# USB_SPI_Flash.net
KiCad netlist of a schematic drawn in Altium Designer
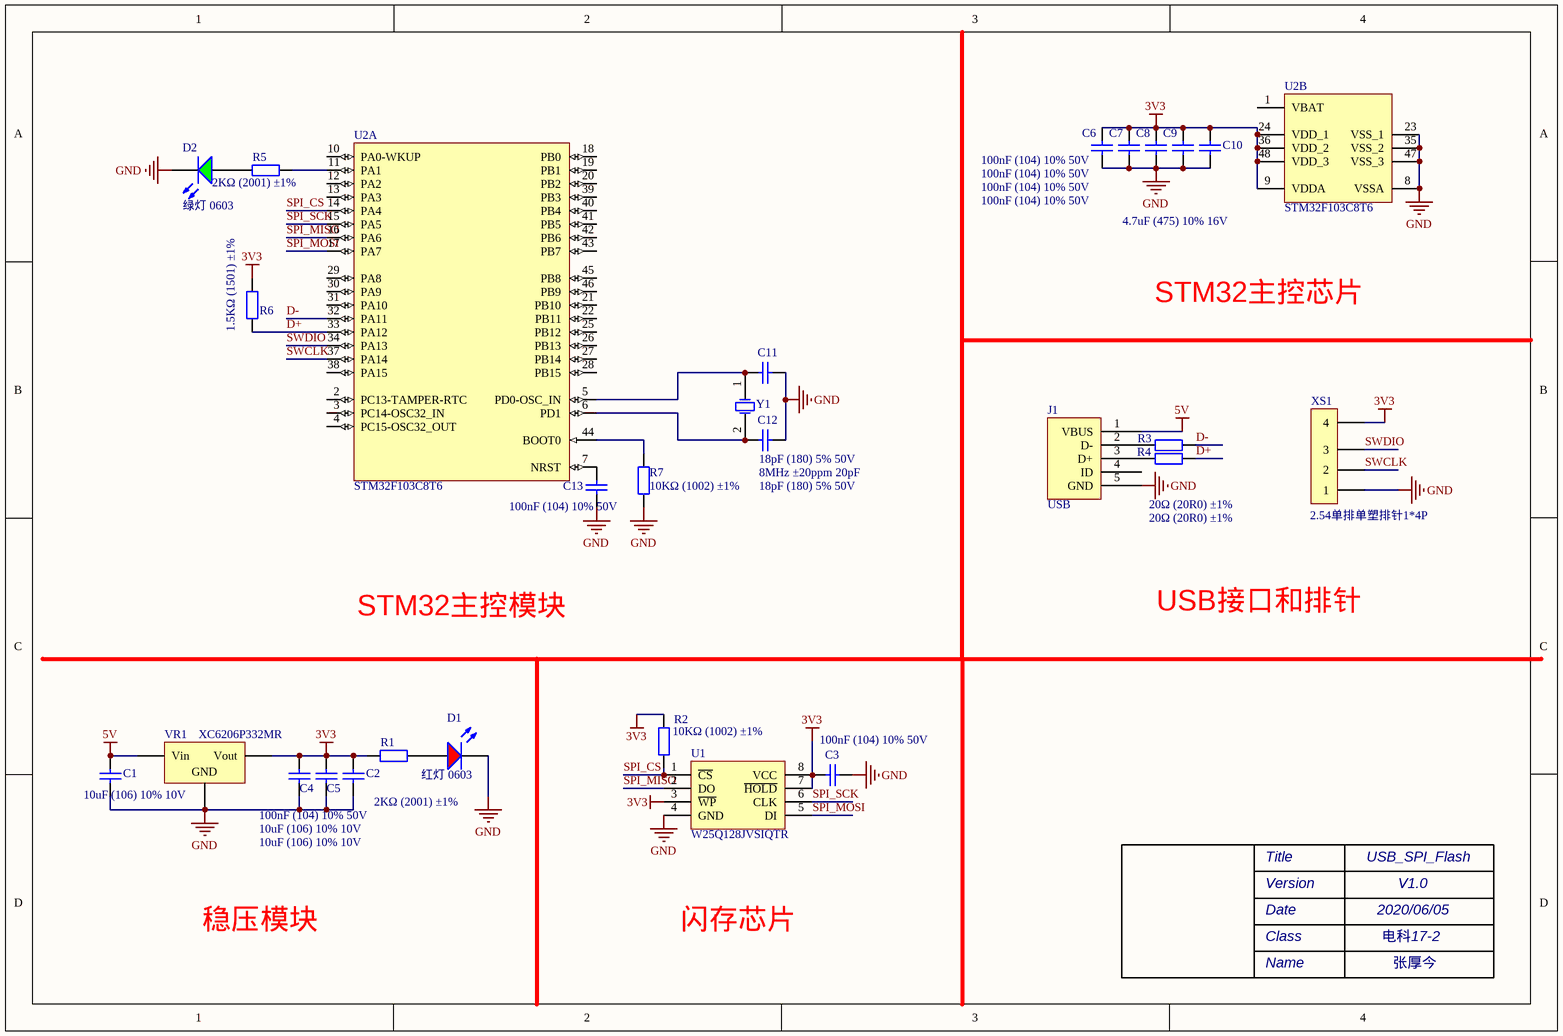
[diagram p0: USB_SPI_Flash.SchDoc]

(export (version "E")
  (design (tool "Eeschema 10.0.6"))
  (components
    (comp (ref "C1")
      (value "10uF (106) 10% 10V")
      (footprint "0603_C")
      (description "贴片电容")
      (libsource (lib "Cap") (part "0603 10uF (106) 10% 10V"))
    )
    (comp (ref "C2")
      (value "100nF (104) 10% 50V")
      (footprint "0603_C")
      (description "贴片电容")
      (libsource (lib "Cap") (part "0603 100nF (104) 10% 50V"))
    )
    (comp (ref "C3")
      (value "100nF (104) 10% 50V")
      (footprint "0603_C")
      (description "贴片电容")
      (libsource (lib "Cap") (part "0603 100nF (104) 10% 50V"))
    )
    (comp (ref "C4")
      (value "10uF (106) 10% 10V")
      (footprint "0603_C")
      (description "贴片电容")
      (libsource (lib "Cap") (part "0603 10uF (106) 10% 10V"))
    )
    (comp (ref "C5")
      (value "10uF (106) 10% 10V")
      (footprint "0603_C")
      (description "贴片电容")
      (libsource (lib "Cap") (part "0603 10uF (106) 10% 10V"))
    )
    (comp (ref "C6")
      (value "100nF (104) 10% 50V")
      (footprint "0603_C")
      (description "贴片电容")
      (libsource (lib "Cap") (part "0603 100nF (104) 10% 50V"))
    )
    (comp (ref "C7")
      (value "100nF (104) 10% 50V")
      (footprint "0603_C")
      (description "贴片电容")
      (libsource (lib "Cap") (part "0603 100nF (104) 10% 50V"))
    )
    (comp (ref "C8")
      (value "100nF (104) 10% 50V")
      (footprint "0603_C")
      (description "贴片电容")
      (libsource (lib "Cap") (part "0603 100nF (104) 10% 50V"))
    )
    (comp (ref "C9")
      (value "100nF (104) 10% 50V")
      (footprint "0603_C")
      (description "贴片电容")
      (libsource (lib "Cap") (part "0603 100nF (104) 10% 50V"))
    )
    (comp (ref "C10")
      (value "4.7uF (475) 10% 16V")
      (footprint "0603_C")
      (description "贴片电容")
      (libsource (lib "Cap") (part "0603 4.7uF (475) 10% 16V"))
    )
    (comp (ref "C11")
      (value "18pF (180) 5% 50V")
      (footprint "0603_C")
      (description "贴片电容")
      (libsource (lib "Cap") (part "0603 18pF (180) 5% 50V"))
    )
    (comp (ref "C12")
      (value "18pF (180) 5% 50V")
      (footprint "0603_C")
      (description "贴片电容")
      (libsource (lib "Cap") (part "0603 18pF (180) 5% 50V"))
    )
    (comp (ref "C13")
      (value "100nF (104) 10% 50V")
      (footprint "0603_C")
      (description "贴片电容")
      (libsource (lib "Cap") (part "0603 100nF (104) 10% 50V"))
    )
    (comp (ref "D1")
      (value "红灯 0603")
      (footprint "0603_LED_S1")
      (description "发光二极管")
      (libsource (lib "LED") (part "0603 红灯"))
    )
    (comp (ref "D2")
      (value "绿灯 0603")
      (footprint "0603_LED_S1")
      (description "发光二极管")
      (libsource (lib "LED") (part "0603 绿灯"))
    )
    (comp (ref "J1")
      (value "USB")
      (footprint "GOLDFIGER_FPC_4")
      (libsource (lib "USB_SPI_Flash") (part "USB"))
    )
    (comp (ref "R1")
      (value "2KΩ (2001) ±1%")
      (footprint "0603_R")
      (description "贴片电阻")
      (libsource (lib "RES") (part "0603 2KΩ (2001) 1%"))
    )
    (comp (ref "R2")
      (value "10KΩ (1002) ±1%")
      (footprint "0603_R")
      (description "贴片电阻")
      (libsource (lib "RES") (part "0603 10KΩ (1002) 1%"))
    )
    (comp (ref "R3")
      (value "20Ω (20R0) ±1%")
      (footprint "0603_R")
      (description "贴片电阻")
      (libsource (lib "RES") (part "0603 20Ω (20R0) 1%"))
    )
    (comp (ref "R4")
      (value "20Ω (20R0) ±1%")
      (footprint "0603_R")
      (description "贴片电阻")
      (libsource (lib "RES") (part "0603 20Ω (20R0) 1%"))
    )
    (comp (ref "R5")
      (value "2KΩ (2001) ±1%")
      (footprint "0603_R")
      (description "贴片电阻")
      (libsource (lib "RES") (part "0603 2KΩ (2001) 1%"))
    )
    (comp (ref "R6")
      (value "1.5KΩ (1501) ±1%")
      (footprint "0603_R")
      (description "贴片电阻")
      (libsource (lib "RES") (part "0603 1.5KΩ (1501) 1%"))
    )
    (comp (ref "R7")
      (value "10KΩ (1002) ±1%")
      (footprint "0603_R")
      (description "贴片电阻")
      (libsource (lib "RES") (part "0603 10KΩ (1002) 1%"))
    )
    (comp (ref "U1")
      (value "W25Q128JVSIQTR")
      (footprint "SOIC-8_208mil")
      (description "Flash ROM")
      (libsource (lib "IC") (part "W25Q128JVSIQTR_[C97521]"))
    )
    (comp (ref "U2")
      (value "STM32F103C8T6")
      (footprint "LQFP-48_7x7x05P")
      (description "ARM")
      (libsource (lib "MCU") (part "STM32F103C8T6"))
    )
    (comp (ref "VR1")
      (value "XC6206P332MR")
      (footprint "SOT-23-3L")
      (description "低压差线性稳压(LDO)")
      (libsource (lib "LDO") (part "SOT-23 XC6206P332MR"))
    )
    (comp (ref "XS1")
      (value "2.54单排单塑排针1*4P")
      (footprint "PIN4")
      (libsource (lib "USB_SPI_Flash") (part "2.54单排单塑排针1*4P"))
    )
    (comp (ref "Y1")
      (value "8MHz ±20ppm 20pF")
      (footprint "SMD-5032_2P")
      (description "贴片晶振")
      (libsource (lib "CrystalOscillator") (part "SMD-5032_2P 8MHz 20ppm 20pF"))
    )
  )
  (nets
    (net (code "1") (name "/D+") (class "Default")
      (node (ref "R4") (pin "2") (pinfunction "2_2") (pintype "passive"))
      (node (ref "R6") (pin "1") (pinfunction "1_1") (pintype "passive"))
      (node (ref "U2") (pin "33") (pinfunction "PA12_33") (pintype "bidirectional"))
    )
    (net (code "2") (name "/D-") (class "Default")
      (node (ref "R3") (pin "2") (pinfunction "2_2") (pintype "passive"))
      (node (ref "U2") (pin "32") (pinfunction "PA11_32") (pintype "bidirectional"))
    )
    (net (code "3") (name "/SPI_CS") (class "Default")
      (node (ref "R2") (pin "1") (pinfunction "1_1") (pintype "passive"))
      (node (ref "U1") (pin "1") (pinfunction "~{CS}_1") (pintype "passive"))
      (node (ref "U2") (pin "14") (pinfunction "PA4_14") (pintype "bidirectional"))
    )
    (net (code "4") (name "/SPI_MISO") (class "Default")
      (node (ref "U1") (pin "2") (pinfunction "DO_2") (pintype "passive"))
      (node (ref "U2") (pin "16") (pinfunction "PA6_16") (pintype "bidirectional"))
    )
    (net (code "5") (name "/SPI_MOSI") (class "Default")
      (node (ref "U1") (pin "5") (pinfunction "DI_5") (pintype "passive"))
      (node (ref "U2") (pin "17") (pinfunction "PA7_17") (pintype "bidirectional"))
    )
    (net (code "6") (name "/SPI_SCK") (class "Default")
      (node (ref "U1") (pin "6") (pinfunction "CLK_6") (pintype "passive"))
      (node (ref "U2") (pin "15") (pinfunction "PA5_15") (pintype "bidirectional"))
    )
    (net (code "7") (name "/SWCLK") (class "Default")
      (node (ref "U2") (pin "37") (pinfunction "PA14_37") (pintype "bidirectional"))
      (node (ref "XS1") (pin "2") (pinfunction "2_2") (pintype "passive"))
    )
    (net (code "8") (name "/SWDIO") (class "Default")
      (node (ref "U2") (pin "34") (pinfunction "PA13_34") (pintype "bidirectional"))
      (node (ref "XS1") (pin "3") (pinfunction "3_3") (pintype "passive"))
    )
    (net (code "9") (name "3V3") (class "Default")
      (node (ref "C10") (pin "2") (pinfunction "2_2") (pintype "passive"))
      (node (ref "C2") (pin "2") (pinfunction "2_2") (pintype "passive"))
      (node (ref "C3") (pin "2") (pinfunction "2_2") (pintype "passive"))
      (node (ref "C4") (pin "2") (pinfunction "2_2") (pintype "passive"))
      (node (ref "C5") (pin "2") (pinfunction "2_2") (pintype "passive"))
      (node (ref "C6") (pin "2") (pinfunction "2_2") (pintype "passive"))
      (node (ref "C7") (pin "2") (pinfunction "2_2") (pintype "passive"))
      (node (ref "C8") (pin "2") (pinfunction "2_2") (pintype "passive"))
      (node (ref "C9") (pin "2") (pinfunction "2_2") (pintype "passive"))
      (node (ref "R1") (pin "2") (pinfunction "2_2") (pintype "passive"))
      (node (ref "R2") (pin "2") (pinfunction "2_2") (pintype "passive"))
      (node (ref "R6") (pin "2") (pinfunction "2_2") (pintype "passive"))
      (node (ref "U1") (pin "3") (pinfunction "~{WP}_3") (pintype "passive"))
      (node (ref "U1") (pin "7") (pinfunction "~{HOLD}_7") (pintype "passive"))
      (node (ref "U1") (pin "8") (pinfunction "VCC_8") (pintype "passive"))
      (node (ref "U2") (pin "24") (pinfunction "VDD_1_24") (pintype "power_in"))
      (node (ref "U2") (pin "36") (pinfunction "VDD_2_36") (pintype "power_in"))
      (node (ref "U2") (pin "48") (pinfunction "VDD_3_48") (pintype "power_in"))
      (node (ref "U2") (pin "9") (pinfunction "VDDA_9") (pintype "power_in"))
      (node (ref "VR1") (pin "2") (pinfunction "Vout_2") (pintype "passive"))
      (node (ref "XS1") (pin "4") (pinfunction "4_4") (pintype "passive"))
    )
    (net (code "10") (name "5V") (class "Default")
      (node (ref "C1") (pin "2") (pinfunction "2_2") (pintype "passive"))
      (node (ref "J1") (pin "1") (pinfunction "VBUS_1") (pintype "passive"))
      (node (ref "VR1") (pin "3") (pinfunction "Vin_3") (pintype "passive"))
    )
    (net (code "11") (name "GND") (class "Default")
      (node (ref "C1") (pin "1") (pinfunction "1_1") (pintype "passive"))
      (node (ref "C10") (pin "1") (pinfunction "1_1") (pintype "passive"))
      (node (ref "C11") (pin "1") (pinfunction "1_1") (pintype "passive"))
      (node (ref "C12") (pin "1") (pinfunction "1_1") (pintype "passive"))
      (node (ref "C13") (pin "1") (pinfunction "1_1") (pintype "passive"))
      (node (ref "C2") (pin "1") (pinfunction "1_1") (pintype "passive"))
      (node (ref "C3") (pin "1") (pinfunction "1_1") (pintype "passive"))
      (node (ref "C4") (pin "1") (pinfunction "1_1") (pintype "passive"))
      (node (ref "C5") (pin "1") (pinfunction "1_1") (pintype "passive"))
      (node (ref "C6") (pin "1") (pinfunction "1_1") (pintype "passive"))
      (node (ref "C7") (pin "1") (pinfunction "1_1") (pintype "passive"))
      (node (ref "C8") (pin "1") (pinfunction "1_1") (pintype "passive"))
      (node (ref "C9") (pin "1") (pinfunction "1_1") (pintype "passive"))
      (node (ref "D1") (pin "K") (pinfunction "K_K") (pintype "passive"))
      (node (ref "D2") (pin "K") (pinfunction "K_K") (pintype "passive"))
      (node (ref "J1") (pin "5") (pinfunction "GND_5") (pintype "passive"))
      (node (ref "R7") (pin "1") (pinfunction "1_1") (pintype "passive"))
      (node (ref "U1") (pin "4") (pinfunction "GND_4") (pintype "passive"))
      (node (ref "U2") (pin "23") (pinfunction "VSS_1_23") (pintype "power_in"))
      (node (ref "U2") (pin "35") (pinfunction "VSS_2_35") (pintype "power_in"))
      (node (ref "U2") (pin "47") (pinfunction "VSS_3_47") (pintype "power_in"))
      (node (ref "U2") (pin "8") (pinfunction "VSSA_8") (pintype "power_in"))
      (node (ref "VR1") (pin "1") (pinfunction "GND_1") (pintype "passive"))
      (node (ref "XS1") (pin "1") (pinfunction "1_1") (pintype "passive"))
    )
    (net (code "12") (name "Net-(D1-PadA)") (class "Default")
      (node (ref "D1") (pin "A") (pinfunction "A_A") (pintype "passive"))
      (node (ref "R1") (pin "1") (pinfunction "1_1") (pintype "passive"))
    )
    (net (code "13") (name "Net-(D2-PadA)") (class "Default")
      (node (ref "D2") (pin "A") (pinfunction "A_A") (pintype "passive"))
      (node (ref "R5") (pin "2") (pinfunction "2_2") (pintype "passive"))
    )
    (net (code "14") (name "Net-(J1-D+)") (class "Default")
      (node (ref "J1") (pin "3") (pinfunction "D+_3") (pintype "passive"))
      (node (ref "R4") (pin "1") (pinfunction "1_1") (pintype "passive"))
    )
    (net (code "15") (name "Net-(J1-D-)") (class "Default")
      (node (ref "J1") (pin "2") (pinfunction "D-_2") (pintype "passive"))
      (node (ref "R3") (pin "1") (pinfunction "1_1") (pintype "passive"))
    )
    (net (code "16") (name "Net-(U2A-BOOT0)") (class "Default")
      (node (ref "R7") (pin "2") (pinfunction "2_2") (pintype "passive"))
      (node (ref "U2") (pin "44") (pinfunction "BOOT0_44") (pintype "input"))
    )
    (net (code "17") (name "Net-(U2A-NRST)") (class "Default")
      (node (ref "C13") (pin "2") (pinfunction "2_2") (pintype "passive"))
      (node (ref "U2") (pin "7") (pinfunction "NRST_7") (pintype "bidirectional"))
    )
    (net (code "18") (name "Net-(U2A-PA1)") (class "Default")
      (node (ref "R5") (pin "1") (pinfunction "1_1") (pintype "passive"))
      (node (ref "U2") (pin "11") (pinfunction "PA1_11") (pintype "bidirectional"))
    )
    (net (code "19") (name "Net-(U2A-PD0-OSC_IN)") (class "Default")
      (node (ref "C11") (pin "2") (pinfunction "2_2") (pintype "passive"))
      (node (ref "U2") (pin "5") (pinfunction "PD0-OSC_IN_5") (pintype "bidirectional"))
      (node (ref "Y1") (pin "1") (pinfunction "OSC1_1") (pintype "passive"))
    )
    (net (code "20") (name "Net-(U2A-PD1)") (class "Default")
      (node (ref "C12") (pin "2") (pinfunction "2_2") (pintype "passive"))
      (node (ref "U2") (pin "6") (pinfunction "PD1_6") (pintype "bidirectional"))
      (node (ref "Y1") (pin "2") (pinfunction "OSC2_2") (pintype "passive"))
    )
    (net (code "21") (name "unconnected-(J1-ID-Pad4)") (class "Default")
      (node (ref "J1") (pin "4") (pinfunction "ID_4") (pintype "passive"))
    )
    (net (code "22") (name "unconnected-(U2A-PA0-WKUP-Pad10)") (class "Default")
      (node (ref "U2") (pin "10") (pinfunction "PA0-WKUP_10") (pintype "bidirectional"))
    )
    (net (code "23") (name "unconnected-(U2A-PA2-Pad12)") (class "Default")
      (node (ref "U2") (pin "12") (pinfunction "PA2_12") (pintype "bidirectional"))
    )
    (net (code "24") (name "unconnected-(U2A-PA3-Pad13)") (class "Default")
      (node (ref "U2") (pin "13") (pinfunction "PA3_13") (pintype "bidirectional"))
    )
    (net (code "25") (name "unconnected-(U2A-PA8-Pad29)") (class "Default")
      (node (ref "U2") (pin "29") (pinfunction "PA8_29") (pintype "bidirectional"))
    )
    (net (code "26") (name "unconnected-(U2A-PA9-Pad30)") (class "Default")
      (node (ref "U2") (pin "30") (pinfunction "PA9_30") (pintype "bidirectional"))
    )
    (net (code "27") (name "unconnected-(U2A-PA10-Pad31)") (class "Default")
      (node (ref "U2") (pin "31") (pinfunction "PA10_31") (pintype "bidirectional"))
    )
    (net (code "28") (name "unconnected-(U2A-PA15-Pad38)") (class "Default")
      (node (ref "U2") (pin "38") (pinfunction "PA15_38") (pintype "bidirectional"))
    )
    (net (code "29") (name "unconnected-(U2A-PB0-Pad18)") (class "Default")
      (node (ref "U2") (pin "18") (pinfunction "PB0_18") (pintype "bidirectional"))
    )
    (net (code "30") (name "unconnected-(U2A-PB1-Pad19)") (class "Default")
      (node (ref "U2") (pin "19") (pinfunction "PB1_19") (pintype "bidirectional"))
    )
    (net (code "31") (name "unconnected-(U2A-PB2-Pad20)") (class "Default")
      (node (ref "U2") (pin "20") (pinfunction "PB2_20") (pintype "bidirectional"))
    )
    (net (code "32") (name "unconnected-(U2A-PB3-Pad39)") (class "Default")
      (node (ref "U2") (pin "39") (pinfunction "PB3_39") (pintype "bidirectional"))
    )
    (net (code "33") (name "unconnected-(U2A-PB4-Pad40)") (class "Default")
      (node (ref "U2") (pin "40") (pinfunction "PB4_40") (pintype "bidirectional"))
    )
    (net (code "34") (name "unconnected-(U2A-PB5-Pad41)") (class "Default")
      (node (ref "U2") (pin "41") (pinfunction "PB5_41") (pintype "bidirectional"))
    )
    (net (code "35") (name "unconnected-(U2A-PB6-Pad42)") (class "Default")
      (node (ref "U2") (pin "42") (pinfunction "PB6_42") (pintype "bidirectional"))
    )
    (net (code "36") (name "unconnected-(U2A-PB7-Pad43)") (class "Default")
      (node (ref "U2") (pin "43") (pinfunction "PB7_43") (pintype "bidirectional"))
    )
    (net (code "37") (name "unconnected-(U2A-PB8-Pad45)") (class "Default")
      (node (ref "U2") (pin "45") (pinfunction "PB8_45") (pintype "bidirectional"))
    )
    (net (code "38") (name "unconnected-(U2A-PB9-Pad46)") (class "Default")
      (node (ref "U2") (pin "46") (pinfunction "PB9_46") (pintype "bidirectional"))
    )
    (net (code "39") (name "unconnected-(U2A-PB10-Pad21)") (class "Default")
      (node (ref "U2") (pin "21") (pinfunction "PB10_21") (pintype "bidirectional"))
    )
    (net (code "40") (name "unconnected-(U2A-PB11-Pad22)") (class "Default")
      (node (ref "U2") (pin "22") (pinfunction "PB11_22") (pintype "bidirectional"))
    )
    (net (code "41") (name "unconnected-(U2A-PB12-Pad25)") (class "Default")
      (node (ref "U2") (pin "25") (pinfunction "PB12_25") (pintype "bidirectional"))
    )
    (net (code "42") (name "unconnected-(U2A-PB13-Pad26)") (class "Default")
      (node (ref "U2") (pin "26") (pinfunction "PB13_26") (pintype "bidirectional"))
    )
    (net (code "43") (name "unconnected-(U2A-PB14-Pad27)") (class "Default")
      (node (ref "U2") (pin "27") (pinfunction "PB14_27") (pintype "bidirectional"))
    )
    (net (code "44") (name "unconnected-(U2A-PB15-Pad28)") (class "Default")
      (node (ref "U2") (pin "28") (pinfunction "PB15_28") (pintype "bidirectional"))
    )
    (net (code "45") (name "unconnected-(U2A-PC13-TAMPER-RTC-Pad2)") (class "Default")
      (node (ref "U2") (pin "2") (pinfunction "PC13-TAMPER-RTC_2") (pintype "bidirectional"))
    )
    (net (code "46") (name "unconnected-(U2A-PC14-OSC32_IN-Pad3)") (class "Default")
      (node (ref "U2") (pin "3") (pinfunction "PC14-OSC32_IN_3") (pintype "bidirectional"))
    )
    (net (code "47") (name "unconnected-(U2A-PC15-OSC32_OUT-Pad4)") (class "Default")
      (node (ref "U2") (pin "4") (pinfunction "PC15-OSC32_OUT_4") (pintype "bidirectional"))
    )
    (net (code "48") (name "unconnected-(U2B-VBAT-Pad1)") (class "Default")
      (node (ref "U2") (pin "1") (pinfunction "VBAT_1") (pintype "power_in"))
    )
  )
)
